# Power_supply.net
KiCad netlist of a schematic drawn in Altium Designer
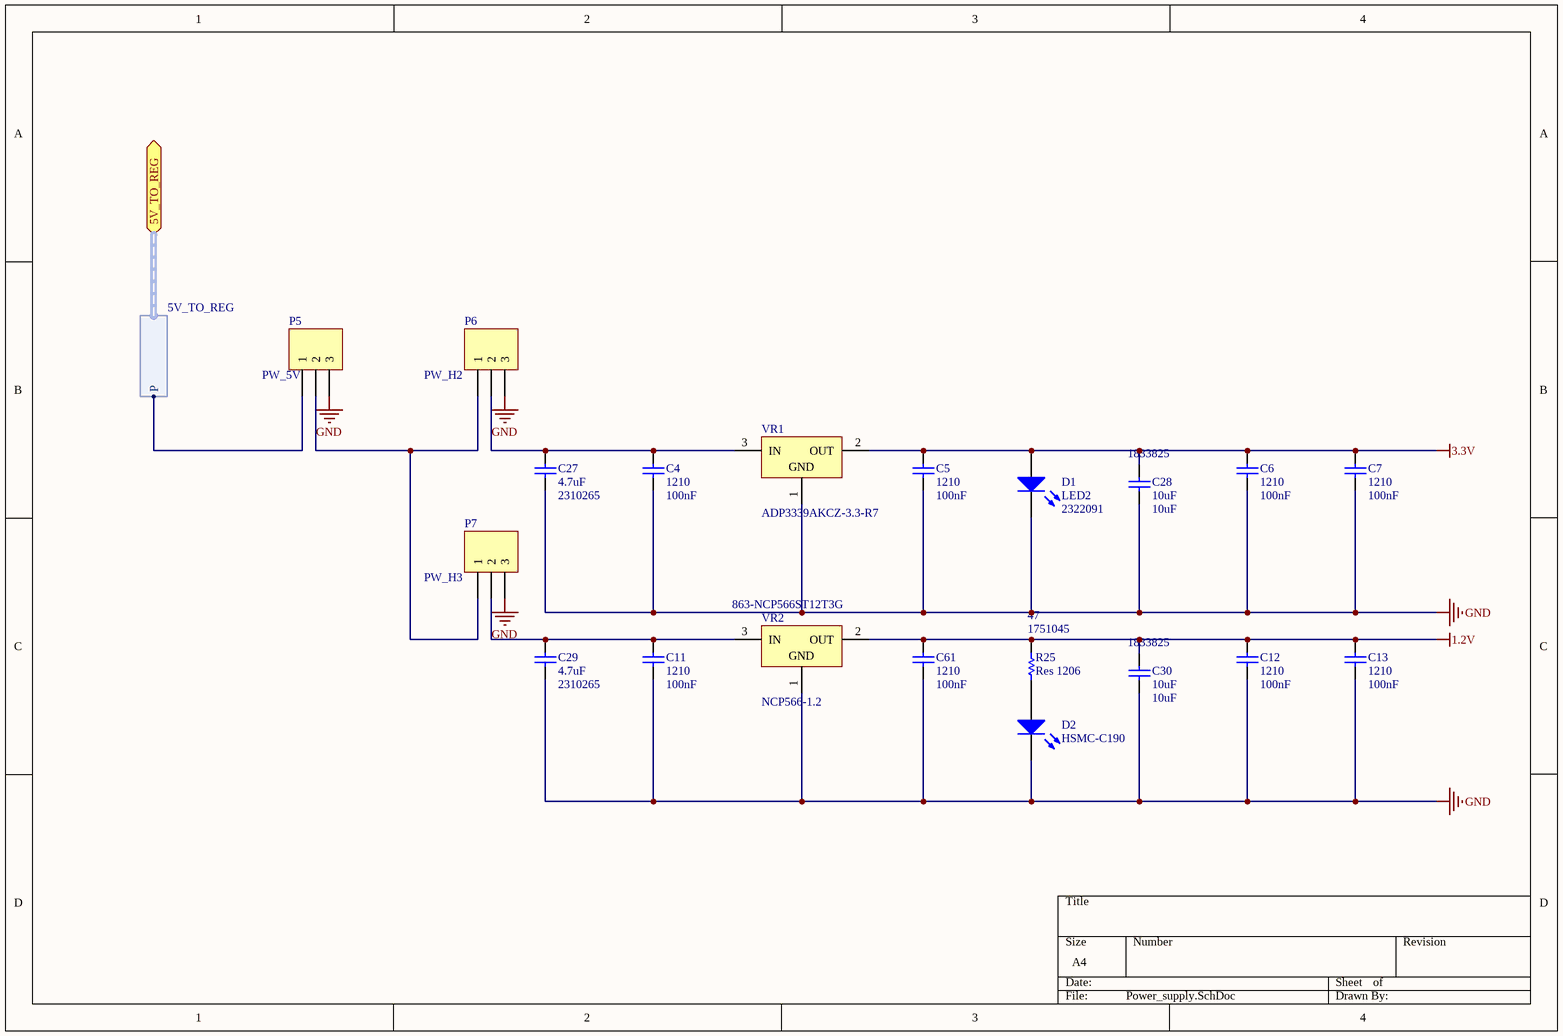
[diagram p0: Power_supply.SchDoc]

(export (version "E")
  (design (tool "Eeschema 10.0.6"))
  (components
    (comp (ref "C4")
      (value "1210")
      (footprint "CAPC1210(3225)105_L")
      (description "CAP 100nF 100V ±5% 1210 (3225 Metric) Thickness 1.05mm SMD")
      (fields (field (name "TOLERANCE") "±5%") (field (name "ALTIUM_VALUE") "100nF"))
      (libsource (lib "Altium Content Vault") (part "CMP-1038-01663-1"))
    )
    (comp (ref "C5")
      (value "1210")
      (footprint "CAPC1210(3225)105_L")
      (description "CAP 100nF 100V ±5% 1210 (3225 Metric) Thickness 1.05mm SMD")
      (fields (field (name "TOLERANCE") "±5%") (field (name "ALTIUM_VALUE") "100nF"))
      (libsource (lib "Altium Content Vault") (part "CMP-1038-01663-1"))
    )
    (comp (ref "C6")
      (value "1210")
      (footprint "CAPC1210(3225)105_L")
      (description "CAP 100nF 100V ±5% 1210 (3225 Metric) Thickness 1.05mm SMD")
      (fields (field (name "TOLERANCE") "±5%") (field (name "ALTIUM_VALUE") "100nF"))
      (libsource (lib "Altium Content Vault") (part "CMP-1038-01663-1"))
    )
    (comp (ref "C7")
      (value "1210")
      (footprint "CAPC1210(3225)105_L")
      (description "CAP 100nF 100V ±5% 1210 (3225 Metric) Thickness 1.05mm SMD")
      (fields (field (name "TOLERANCE") "±5%") (field (name "ALTIUM_VALUE") "100nF"))
      (libsource (lib "Altium Content Vault") (part "CMP-1038-01663-1"))
    )
    (comp (ref "C11")
      (value "1210")
      (footprint "CAPC1210(3225)105_L")
      (description "CAP 100nF 100V ±5% 1210 (3225 Metric) Thickness 1.05mm SMD")
      (fields (field (name "TOLERANCE") "±5%") (field (name "ALTIUM_VALUE") "100nF"))
      (libsource (lib "Altium Content Vault") (part "CMP-1038-01663-1"))
    )
    (comp (ref "C12")
      (value "1210")
      (footprint "CAPC1210(3225)105_L")
      (description "CAP 100nF 100V ±5% 1210 (3225 Metric) Thickness 1.05mm SMD")
      (fields (field (name "TOLERANCE") "±5%") (field (name "ALTIUM_VALUE") "100nF"))
      (libsource (lib "Altium Content Vault") (part "CMP-1038-01663-1"))
    )
    (comp (ref "C13")
      (value "1210")
      (footprint "CAPC1210(3225)105_L")
      (description "CAP 100nF 100V ±5% 1210 (3225 Metric) Thickness 1.05mm SMD")
      (fields (field (name "TOLERANCE") "±5%") (field (name "ALTIUM_VALUE") "100nF"))
      (libsource (lib "Altium Content Vault") (part "CMP-1038-01663-1"))
    )
    (comp (ref "C27")
      (value "4.7uF")
      (footprint "C1206")
      (description "Capacitor (Semiconductor SIM Model)")
      (fields
        (field (name "SUPPLIER PART NUMBER 1") "2310265")
        (field (name "MANUFACTURER") "AVX")
        (field (name "MANUFACTURER PART NUMBER") "12061Z475KAT2A")
        (field (name "PUBLISHER") "Altium Limited")
      )
      (libsource (lib "Miscellaneous Devices") (part "Cap Semi"))
    )
    (comp (ref "C28")
      (value "10uF")
      (footprint "C1206")
      (description "Capacitor (Semiconductor SIM Model)")
      (fields
        (field (name "ALTIUM_VALUE") "10uF")
        (field (name "SUPPLIER PART NUMBER 1") "1833825")
        (field (name "MANUFACTURER") "AVX")
        (field (name "MANUFACTURER PART NUMBER") "12063D106KAT2A")
        (field (name "PUBLISHER") "Altium Limited")
      )
      (libsource (lib "Miscellaneous Devices") (part "Cap Semi"))
    )
    (comp (ref "C29")
      (value "4.7uF")
      (footprint "C1206")
      (description "Capacitor (Semiconductor SIM Model)")
      (fields
        (field (name "SUPPLIER PART NUMBER 1") "2310265")
        (field (name "MANUFACTURER") "AVX")
        (field (name "MANUFACTURER PART NUMBER") "12061Z475KAT2A")
        (field (name "PUBLISHER") "Altium Limited")
      )
      (libsource (lib "Miscellaneous Devices") (part "Cap Semi"))
    )
    (comp (ref "C30")
      (value "10uF")
      (footprint "C1206")
      (description "Capacitor (Semiconductor SIM Model)")
      (fields
        (field (name "ALTIUM_VALUE") "10uF")
        (field (name "SUPPLIER PART NUMBER 1") "1833825")
        (field (name "MANUFACTURER") "AVX")
        (field (name "MANUFACTURER PART NUMBER") "12063D106KAT2A")
        (field (name "PUBLISHER") "Altium Limited")
      )
      (libsource (lib "Miscellaneous Devices") (part "Cap Semi"))
    )
    (comp (ref "C61")
      (value "1210")
      (footprint "CAPC1210(3225)105_L")
      (description "CAP 100nF 100V ±5% 1210 (3225 Metric) Thickness 1.05mm SMD")
      (fields (field (name "TOLERANCE") "±5%") (field (name "ALTIUM_VALUE") "100nF"))
      (libsource (lib "Altium Content Vault") (part "CMP-1038-01663-1"))
    )
    (comp (ref "D1")
      (value "LED2")
      (footprint "C1206")
      (description "Typical RED, GREEN, YELLOW, AMBER GaAs LED")
      (fields
        (field (name "SUPPLIER PART NUMBER 1") "2322091")
        (field (name "MANUFACTURER") "WURTH ELEKTRONIK")
        (field (name "MANUFACTURER PART NUMBER") "156120GS75300")
        (field (name "PUBLISHER") "Altium Limited")
      )
      (libsource (lib "Miscellaneous Devices") (part "LED2"))
    )
    (comp (ref "D2")
      (value "HSMC-C190")
      (footprint "1.6X0.8X0.8")
      (description "High Performance Chip LED, Red")
      (fields (field (name "PUBLISHER") "Altium Limited"))
      (libsource (lib "Avago Optoelectronic LED") (part "HSMC-C190"))
    )
    (comp (ref "P5")
      (value "PW_5V")
      (footprint "HDR1X3")
      (description "Header, 3-Pin")
      (fields (field (name "PUBLISHER") "Altium Limited"))
      (libsource (lib "Miscellaneous Connectors") (part "Header 3"))
    )
    (comp (ref "P6")
      (value "PW_H2")
      (footprint "HDR1X3")
      (description "Header, 3-Pin")
      (fields (field (name "PUBLISHER") "Altium Limited"))
      (libsource (lib "Miscellaneous Connectors") (part "Header 3"))
    )
    (comp (ref "P7")
      (value "PW_H3")
      (footprint "HDR1X3")
      (description "Header, 3-Pin")
      (fields (field (name "PUBLISHER") "Altium Limited"))
      (libsource (lib "Miscellaneous Connectors") (part "Header 3"))
    )
    (comp (ref "R25")
      (value "Res 1206")
      (footprint "RESC1206(3216)_L")
      (description "105R 0.25W 5% 1206 (3216 Metric)  SMD")
      (fields
        (field (name "TOLERANCE") "5 %")
        (field (name "POWER") "0.25 W")
        (field (name "SUPPLIER PART NUMBER 1") "1751045")
        (field (name "RESISTANCE") "47")
      )
      (libsource (lib "Altium Content Vault") (part "CMP-1014-00056-1"))
    )
    (comp (ref "VR1")
      (value "ADP3339AKCZ-3.3-R7")
      (footprint "ADI-KC-3_M")
      (fields (field (name "MANUFACTURER") "Analog Devices"))
      (libsource (lib "Altium Content Vault") (part "CMP-0786-00156-1"))
    )
    (comp (ref "VR2")
      (value "NCP566-1.2")
      (footprint "SOT223_N")
      (description "5A Low Dropout Positive Regulators, 3-pin TO-220")
      (fields
        (field (name "SUPPLIER PART NUMBER 1") "863-NCP566ST12T3G")
        (field (name "MANUFACTURER") "ON Semiconductor")
        (field (name "MANUFACTURER PART NUMBER") "NCP566ST12T3G")
      )
      (libsource (lib "NSC LDO") (part "LM1084IT-3.3"))
    )
  )
  (nets
    (net (code "1") (name "/P") (class "Default")
      (node (ref "P5") (pin "1") (pinfunction "1_1") (pintype "passive"))
    )
    (net (code "2") (name "1.2V") (class "Default")
      (node (ref "C12") (pin "2") (pinfunction "2_2") (pintype "passive"))
      (node (ref "C13") (pin "2") (pinfunction "2_2") (pintype "passive"))
      (node (ref "C30") (pin "2") (pinfunction "2_2") (pintype "passive"))
      (node (ref "C61") (pin "2") (pinfunction "2_2") (pintype "passive"))
      (node (ref "R25") (pin "1") (pinfunction "1_1") (pintype "passive"))
      (node (ref "VR2") (pin "2") (pinfunction "OUT_2") (pintype "power_in"))
    )
    (net (code "3") (name "3.3V") (class "Default")
      (node (ref "C28") (pin "2") (pinfunction "2_2") (pintype "passive"))
      (node (ref "C5") (pin "2") (pinfunction "2_2") (pintype "passive"))
      (node (ref "C6") (pin "2") (pinfunction "2_2") (pintype "passive"))
      (node (ref "C7") (pin "2") (pinfunction "2_2") (pintype "passive"))
      (node (ref "D1") (pin "1") (pinfunction "A_1") (pintype "passive"))
      (node (ref "VR1") (pin "2") (pinfunction "OUT_2") (pintype "power_in"))
    )
    (net (code "4") (name "GND") (class "Default")
      (node (ref "C11") (pin "1") (pinfunction "1_1") (pintype "passive"))
      (node (ref "C12") (pin "1") (pinfunction "1_1") (pintype "passive"))
      (node (ref "C13") (pin "1") (pinfunction "1_1") (pintype "passive"))
      (node (ref "C27") (pin "1") (pinfunction "1_1") (pintype "passive"))
      (node (ref "C28") (pin "1") (pinfunction "1_1") (pintype "passive"))
      (node (ref "C29") (pin "1") (pinfunction "1_1") (pintype "passive"))
      (node (ref "C30") (pin "1") (pinfunction "1_1") (pintype "passive"))
      (node (ref "C4") (pin "1") (pinfunction "1_1") (pintype "passive"))
      (node (ref "C5") (pin "1") (pinfunction "1_1") (pintype "passive"))
      (node (ref "C6") (pin "1") (pinfunction "1_1") (pintype "passive"))
      (node (ref "C61") (pin "1") (pinfunction "1_1") (pintype "passive"))
      (node (ref "C7") (pin "1") (pinfunction "1_1") (pintype "passive"))
      (node (ref "D1") (pin "2") (pinfunction "K_2") (pintype "passive"))
      (node (ref "D2") (pin "2") (pinfunction "K_2") (pintype "passive"))
      (node (ref "P5") (pin "3") (pinfunction "3_3") (pintype "passive"))
      (node (ref "P6") (pin "3") (pinfunction "3_3") (pintype "passive"))
      (node (ref "P7") (pin "3") (pinfunction "3_3") (pintype "passive"))
      (node (ref "VR1") (pin "1") (pinfunction "GND_1") (pintype "power_in"))
      (node (ref "VR2") (pin "1") (pinfunction "GND_1") (pintype "power_in"))
    )
    (net (code "5") (name "Net-(D2-A)") (class "Default")
      (node (ref "D2") (pin "1") (pinfunction "A_1") (pintype "passive"))
      (node (ref "R25") (pin "2") (pinfunction "2_2") (pintype "passive"))
    )
    (net (code "6") (name "Net-(P5-Pad2)") (class "Default")
      (node (ref "P5") (pin "2") (pinfunction "2_2") (pintype "passive"))
      (node (ref "P6") (pin "1") (pinfunction "1_1") (pintype "passive"))
      (node (ref "P7") (pin "1") (pinfunction "1_1") (pintype "passive"))
    )
    (net (code "7") (name "Net-(VR1-IN)") (class "Default")
      (node (ref "C27") (pin "2") (pinfunction "2_2") (pintype "passive"))
      (node (ref "C4") (pin "2") (pinfunction "2_2") (pintype "passive"))
      (node (ref "P6") (pin "2") (pinfunction "2_2") (pintype "passive"))
      (node (ref "VR1") (pin "3") (pinfunction "IN_3") (pintype "power_in"))
    )
    (net (code "8") (name "Net-(VR2-IN)") (class "Default")
      (node (ref "C11") (pin "2") (pinfunction "2_2") (pintype "passive"))
      (node (ref "C29") (pin "2") (pinfunction "2_2") (pintype "passive"))
      (node (ref "P7") (pin "2") (pinfunction "2_2") (pintype "passive"))
      (node (ref "VR2") (pin "3") (pinfunction "IN_3") (pintype "power_in"))
    )
  )
)
